# FOS-00_Rev_1_3.net
KiCad netlist of a schematic drawn in Altium Designer
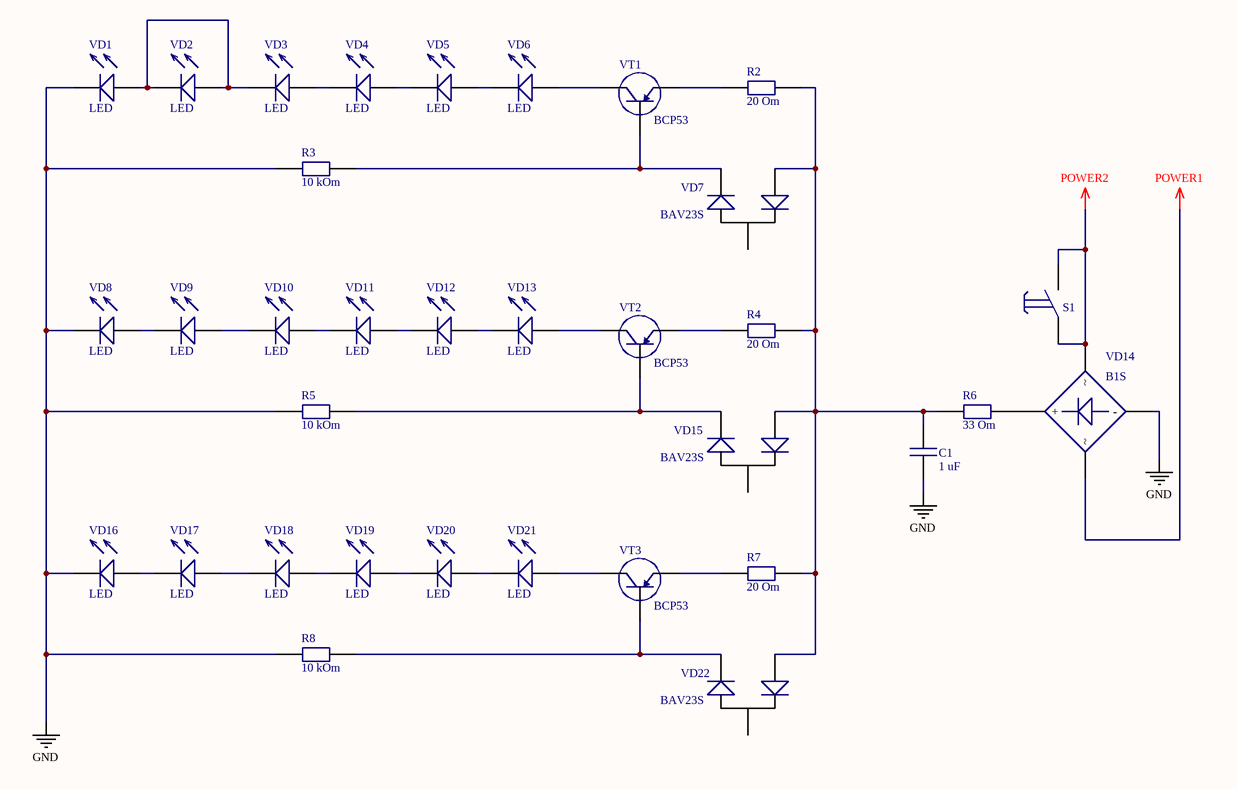
[diagram p0: FOS-00 Rev 1_3.SchDoc]

(export (version "E")
  (design (tool "Eeschema 10.0.6"))
  (components
    (comp (ref "C1")
      (value "1 uF")
      (footprint "CAP1206")
      (fields (field (name "Comment") "Capacitor"))
      (libsource (lib "my_library") (part "Capacitor"))
    )
    (comp (ref "R2")
      (value "20 Om")
      (footprint "RES1206")
      (fields (field (name "Comment") "Resistor"))
      (libsource (lib "my_library") (part "Resistor"))
    )
    (comp (ref "R3")
      (value "10 kOm")
      (footprint "RES1206")
      (fields (field (name "Comment") "Resistor"))
      (libsource (lib "my_library") (part "Resistor"))
    )
    (comp (ref "R4")
      (value "20 Om")
      (footprint "RES1206")
      (fields (field (name "Comment") "Resistor"))
      (libsource (lib "my_library") (part "Resistor"))
    )
    (comp (ref "R5")
      (value "10 kOm")
      (footprint "RES1206")
      (fields (field (name "Comment") "Resistor"))
      (libsource (lib "my_library") (part "Resistor"))
    )
    (comp (ref "R6")
      (value "33 Om")
      (footprint "RES1206")
      (fields (field (name "Comment") "Resistor"))
      (libsource (lib "my_library") (part "Resistor"))
    )
    (comp (ref "R7")
      (value "20 Om")
      (footprint "RES1206")
      (fields (field (name "Comment") "Resistor"))
      (libsource (lib "my_library") (part "Resistor"))
    )
    (comp (ref "R8")
      (value "10 kOm")
      (footprint "RES1206")
      (fields (field (name "Comment") "Resistor"))
      (libsource (lib "my_library") (part "Resistor"))
    )
    (comp (ref "S1") (value "button") (footprint "button1") (libsource (lib "my_library") (part "button")))
    (comp (ref "VD1") (value "LED") (footprint "LED_SAKURA") (libsource (lib "my_library") (part "LED")))
    (comp (ref "VD2") (value "LED") (footprint "LED_SAKURA") (libsource (lib "my_library") (part "LED")))
    (comp (ref "VD3") (value "LED") (footprint "LED_SAKURA") (libsource (lib "my_library") (part "LED")))
    (comp (ref "VD4") (value "LED") (footprint "LED_SAKURA") (libsource (lib "my_library") (part "LED")))
    (comp (ref "VD5") (value "LED") (footprint "LED_SAKURA") (libsource (lib "my_library") (part "LED")))
    (comp (ref "VD6") (value "LED") (footprint "LED_SAKURA") (libsource (lib "my_library") (part "LED")))
    (comp (ref "VD7") (value "BAV23S") (footprint "SOT 23") (libsource (lib "my_library") (part "BAV23S")))
    (comp (ref "VD8") (value "LED") (footprint "LED_SAKURA") (libsource (lib "my_library") (part "LED")))
    (comp (ref "VD9") (value "LED") (footprint "LED_SAKURA") (libsource (lib "my_library") (part "LED")))
    (comp (ref "VD10") (value "LED") (footprint "LED_SAKURA") (libsource (lib "my_library") (part "LED")))
    (comp (ref "VD11") (value "LED") (footprint "LED_SAKURA") (libsource (lib "my_library") (part "LED")))
    (comp (ref "VD12") (value "LED") (footprint "LED_SAKURA") (libsource (lib "my_library") (part "LED")))
    (comp (ref "VD13") (value "LED") (footprint "LED_SAKURA") (libsource (lib "my_library") (part "LED")))
    (comp (ref "VD14")
      (value "B1S")
      (footprint "db-1ms")
      (fields (field (name "Comment") "Diode Bridge"))
      (libsource (lib "my_library") (part "Diode Bridge"))
    )
    (comp (ref "VD15") (value "BAV23S") (footprint "SOT 23") (libsource (lib "my_library") (part "BAV23S")))
    (comp (ref "VD16") (value "LED") (footprint "LED_SAKURA") (libsource (lib "my_library") (part "LED")))
    (comp (ref "VD17") (value "LED") (footprint "LED_SAKURA") (libsource (lib "my_library") (part "LED")))
    (comp (ref "VD18") (value "LED") (footprint "LED_SAKURA") (libsource (lib "my_library") (part "LED")))
    (comp (ref "VD19") (value "LED") (footprint "LED_SAKURA") (libsource (lib "my_library") (part "LED")))
    (comp (ref "VD20") (value "LED") (footprint "LED_SAKURA") (libsource (lib "my_library") (part "LED")))
    (comp (ref "VD21") (value "LED") (footprint "LED_SAKURA") (libsource (lib "my_library") (part "LED")))
    (comp (ref "VD22") (value "BAV23S") (footprint "SOT 23") (libsource (lib "my_library") (part "BAV23S")))
    (comp (ref "VT1")
      (value "BCP53")
      (footprint "SOT223")
      (fields (field (name "Comment") "PNP"))
      (libsource (lib "my_library") (part "PNP"))
    )
    (comp (ref "VT2")
      (value "BCP53")
      (footprint "SOT223")
      (fields (field (name "Comment") "PNP"))
      (libsource (lib "my_library") (part "PNP"))
    )
    (comp (ref "VT3")
      (value "BCP53")
      (footprint "SOT223")
      (fields (field (name "Comment") "PNP"))
      (libsource (lib "my_library") (part "PNP"))
    )
  )
  (nets
    (net (code "1") (name "GND") (class "Default")
      (node (ref "C1") (pin "1") (pinfunction "1_1") (pintype "passive"))
      (node (ref "R3") (pin "1") (pinfunction "1_1") (pintype "passive"))
      (node (ref "R5") (pin "1") (pinfunction "1_1") (pintype "passive"))
      (node (ref "R8") (pin "1") (pinfunction "1_1") (pintype "passive"))
      (node (ref "VD1") (pin "1") (pinfunction "1_1") (pintype "passive"))
      (node (ref "VD14") (pin "2") (pinfunction "-_2") (pintype "passive"))
      (node (ref "VD16") (pin "1") (pinfunction "1_1") (pintype "passive"))
      (node (ref "VD8") (pin "1") (pinfunction "1_1") (pintype "passive"))
    )
    (net (code "2") (name "Net-(C1-Pad2)") (class "Default")
      (node (ref "C1") (pin "2") (pinfunction "2_2") (pintype "passive"))
      (node (ref "R2") (pin "2") (pinfunction "2_2") (pintype "passive"))
      (node (ref "R4") (pin "2") (pinfunction "2_2") (pintype "passive"))
      (node (ref "R6") (pin "1") (pinfunction "1_1") (pintype "passive"))
      (node (ref "R7") (pin "2") (pinfunction "2_2") (pintype "passive"))
      (node (ref "VD15") (pin "1") (pinfunction "1_1") (pintype "passive"))
      (node (ref "VD22") (pin "1") (pinfunction "1_1") (pintype "passive"))
      (node (ref "VD7") (pin "1") (pinfunction "1_1") (pintype "passive"))
    )
    (net (code "3") (name "Net-(R2-Pad1)") (class "Default")
      (node (ref "R2") (pin "1") (pinfunction "1_1") (pintype "passive"))
      (node (ref "VT1") (pin "E") (pinfunction "E_E") (pintype "passive"))
    )
    (net (code "4") (name "Net-(R3-Pad2)") (class "Default")
      (node (ref "R3") (pin "2") (pinfunction "2_2") (pintype "passive"))
      (node (ref "VD7") (pin "2") (pinfunction "2_2") (pintype "passive"))
      (node (ref "VT1") (pin "B") (pinfunction "B_B") (pintype "passive"))
    )
    (net (code "5") (name "Net-(R4-Pad1)") (class "Default")
      (node (ref "R4") (pin "1") (pinfunction "1_1") (pintype "passive"))
      (node (ref "VT2") (pin "E") (pinfunction "E_E") (pintype "passive"))
    )
    (net (code "6") (name "Net-(R5-Pad2)") (class "Default")
      (node (ref "R5") (pin "2") (pinfunction "2_2") (pintype "passive"))
      (node (ref "VD15") (pin "2") (pinfunction "2_2") (pintype "passive"))
      (node (ref "VT2") (pin "B") (pinfunction "B_B") (pintype "passive"))
    )
    (net (code "7") (name "Net-(R7-Pad1)") (class "Default")
      (node (ref "R7") (pin "1") (pinfunction "1_1") (pintype "passive"))
      (node (ref "VT3") (pin "E") (pinfunction "E_E") (pintype "passive"))
    )
    (net (code "8") (name "Net-(R8-Pad2)") (class "Default")
      (node (ref "R8") (pin "2") (pinfunction "2_2") (pintype "passive"))
      (node (ref "VD22") (pin "2") (pinfunction "2_2") (pintype "passive"))
      (node (ref "VT3") (pin "B") (pinfunction "B_B") (pintype "passive"))
    )
    (net (code "9") (name "Net-(VD1-Pad2)") (class "Default")
      (node (ref "VD1") (pin "2") (pinfunction "2_2") (pintype "passive"))
      (node (ref "VD2") (pin "1") (pinfunction "1_1") (pintype "passive"))
      (node (ref "VD2") (pin "2") (pinfunction "2_2") (pintype "passive"))
      (node (ref "VD3") (pin "1") (pinfunction "1_1") (pintype "passive"))
    )
    (net (code "10") (name "Net-(VD3-Pad2)") (class "Default")
      (node (ref "VD3") (pin "2") (pinfunction "2_2") (pintype "passive"))
      (node (ref "VD4") (pin "1") (pinfunction "1_1") (pintype "passive"))
    )
    (net (code "11") (name "Net-(VD4-Pad2)") (class "Default")
      (node (ref "VD4") (pin "2") (pinfunction "2_2") (pintype "passive"))
      (node (ref "VD5") (pin "1") (pinfunction "1_1") (pintype "passive"))
    )
    (net (code "12") (name "Net-(VD5-Pad2)") (class "Default")
      (node (ref "VD5") (pin "2") (pinfunction "2_2") (pintype "passive"))
      (node (ref "VD6") (pin "1") (pinfunction "1_1") (pintype "passive"))
    )
    (net (code "13") (name "Net-(VD6-Pad2)") (class "Default")
      (node (ref "VD6") (pin "2") (pinfunction "2_2") (pintype "passive"))
      (node (ref "VT1") (pin "K") (pinfunction "K_K") (pintype "passive"))
    )
    (net (code "14") (name "Net-(VD8-Pad2)") (class "Default")
      (node (ref "VD8") (pin "2") (pinfunction "2_2") (pintype "passive"))
      (node (ref "VD9") (pin "1") (pinfunction "1_1") (pintype "passive"))
    )
    (net (code "15") (name "Net-(VD10-Pad1)") (class "Default")
      (node (ref "VD10") (pin "1") (pinfunction "1_1") (pintype "passive"))
      (node (ref "VD9") (pin "2") (pinfunction "2_2") (pintype "passive"))
    )
    (net (code "16") (name "Net-(VD10-Pad2)") (class "Default")
      (node (ref "VD10") (pin "2") (pinfunction "2_2") (pintype "passive"))
      (node (ref "VD11") (pin "1") (pinfunction "1_1") (pintype "passive"))
    )
    (net (code "17") (name "Net-(VD11-Pad2)") (class "Default")
      (node (ref "VD11") (pin "2") (pinfunction "2_2") (pintype "passive"))
      (node (ref "VD12") (pin "1") (pinfunction "1_1") (pintype "passive"))
    )
    (net (code "18") (name "Net-(VD12-Pad2)") (class "Default")
      (node (ref "VD12") (pin "2") (pinfunction "2_2") (pintype "passive"))
      (node (ref "VD13") (pin "1") (pinfunction "1_1") (pintype "passive"))
    )
    (net (code "19") (name "Net-(VD13-Pad2)") (class "Default")
      (node (ref "VD13") (pin "2") (pinfunction "2_2") (pintype "passive"))
      (node (ref "VT2") (pin "K") (pinfunction "K_K") (pintype "passive"))
    )
    (net (code "20") (name "Net-(VD14-+)") (class "Default")
      (node (ref "R6") (pin "2") (pinfunction "2_2") (pintype "passive"))
      (node (ref "VD14") (pin "1") (pinfunction "+_1") (pintype "passive"))
    )
    (net (code "21") (name "Net-(VD16-Pad2)") (class "Default")
      (node (ref "VD16") (pin "2") (pinfunction "2_2") (pintype "passive"))
      (node (ref "VD17") (pin "1") (pinfunction "1_1") (pintype "passive"))
    )
    (net (code "22") (name "Net-(VD17-Pad2)") (class "Default")
      (node (ref "VD17") (pin "2") (pinfunction "2_2") (pintype "passive"))
      (node (ref "VD18") (pin "1") (pinfunction "1_1") (pintype "passive"))
    )
    (net (code "23") (name "Net-(VD18-Pad2)") (class "Default")
      (node (ref "VD18") (pin "2") (pinfunction "2_2") (pintype "passive"))
      (node (ref "VD19") (pin "1") (pinfunction "1_1") (pintype "passive"))
    )
    (net (code "24") (name "Net-(VD19-Pad2)") (class "Default")
      (node (ref "VD19") (pin "2") (pinfunction "2_2") (pintype "passive"))
      (node (ref "VD20") (pin "1") (pinfunction "1_1") (pintype "passive"))
    )
    (net (code "25") (name "Net-(VD20-Pad2)") (class "Default")
      (node (ref "VD20") (pin "2") (pinfunction "2_2") (pintype "passive"))
      (node (ref "VD21") (pin "1") (pinfunction "1_1") (pintype "passive"))
    )
    (net (code "26") (name "Net-(VD21-Pad2)") (class "Default")
      (node (ref "VD21") (pin "2") (pinfunction "2_2") (pintype "passive"))
      (node (ref "VT3") (pin "K") (pinfunction "K_K") (pintype "passive"))
    )
    (net (code "27") (name "POWER1") (class "Default")
      (node (ref "VD14") (pin "3") (pinfunction "~_3") (pintype "passive"))
    )
    (net (code "28") (name "POWER2") (class "Default")
      (node (ref "S1") (pin "1") (pinfunction "1_1") (pintype "passive"))
      (node (ref "S1") (pin "2") (pinfunction "2_2") (pintype "passive"))
      (node (ref "VD14") (pin "4") (pinfunction "~_4") (pintype "passive"))
    )
    (net (code "29") (name "unconnected-(VD7-Pad3)") (class "Default")
      (node (ref "VD7") (pin "3") (pinfunction "3_3") (pintype "passive"))
    )
    (net (code "30") (name "unconnected-(VD15-Pad3)") (class "Default")
      (node (ref "VD15") (pin "3") (pinfunction "3_3") (pintype "passive"))
    )
    (net (code "31") (name "unconnected-(VD22-Pad3)") (class "Default")
      (node (ref "VD22") (pin "3") (pinfunction "3_3") (pintype "passive"))
    )
  )
)
